# F50_cryocooler_controller.net
KiCad netlist of a schematic drawn in EAGLE
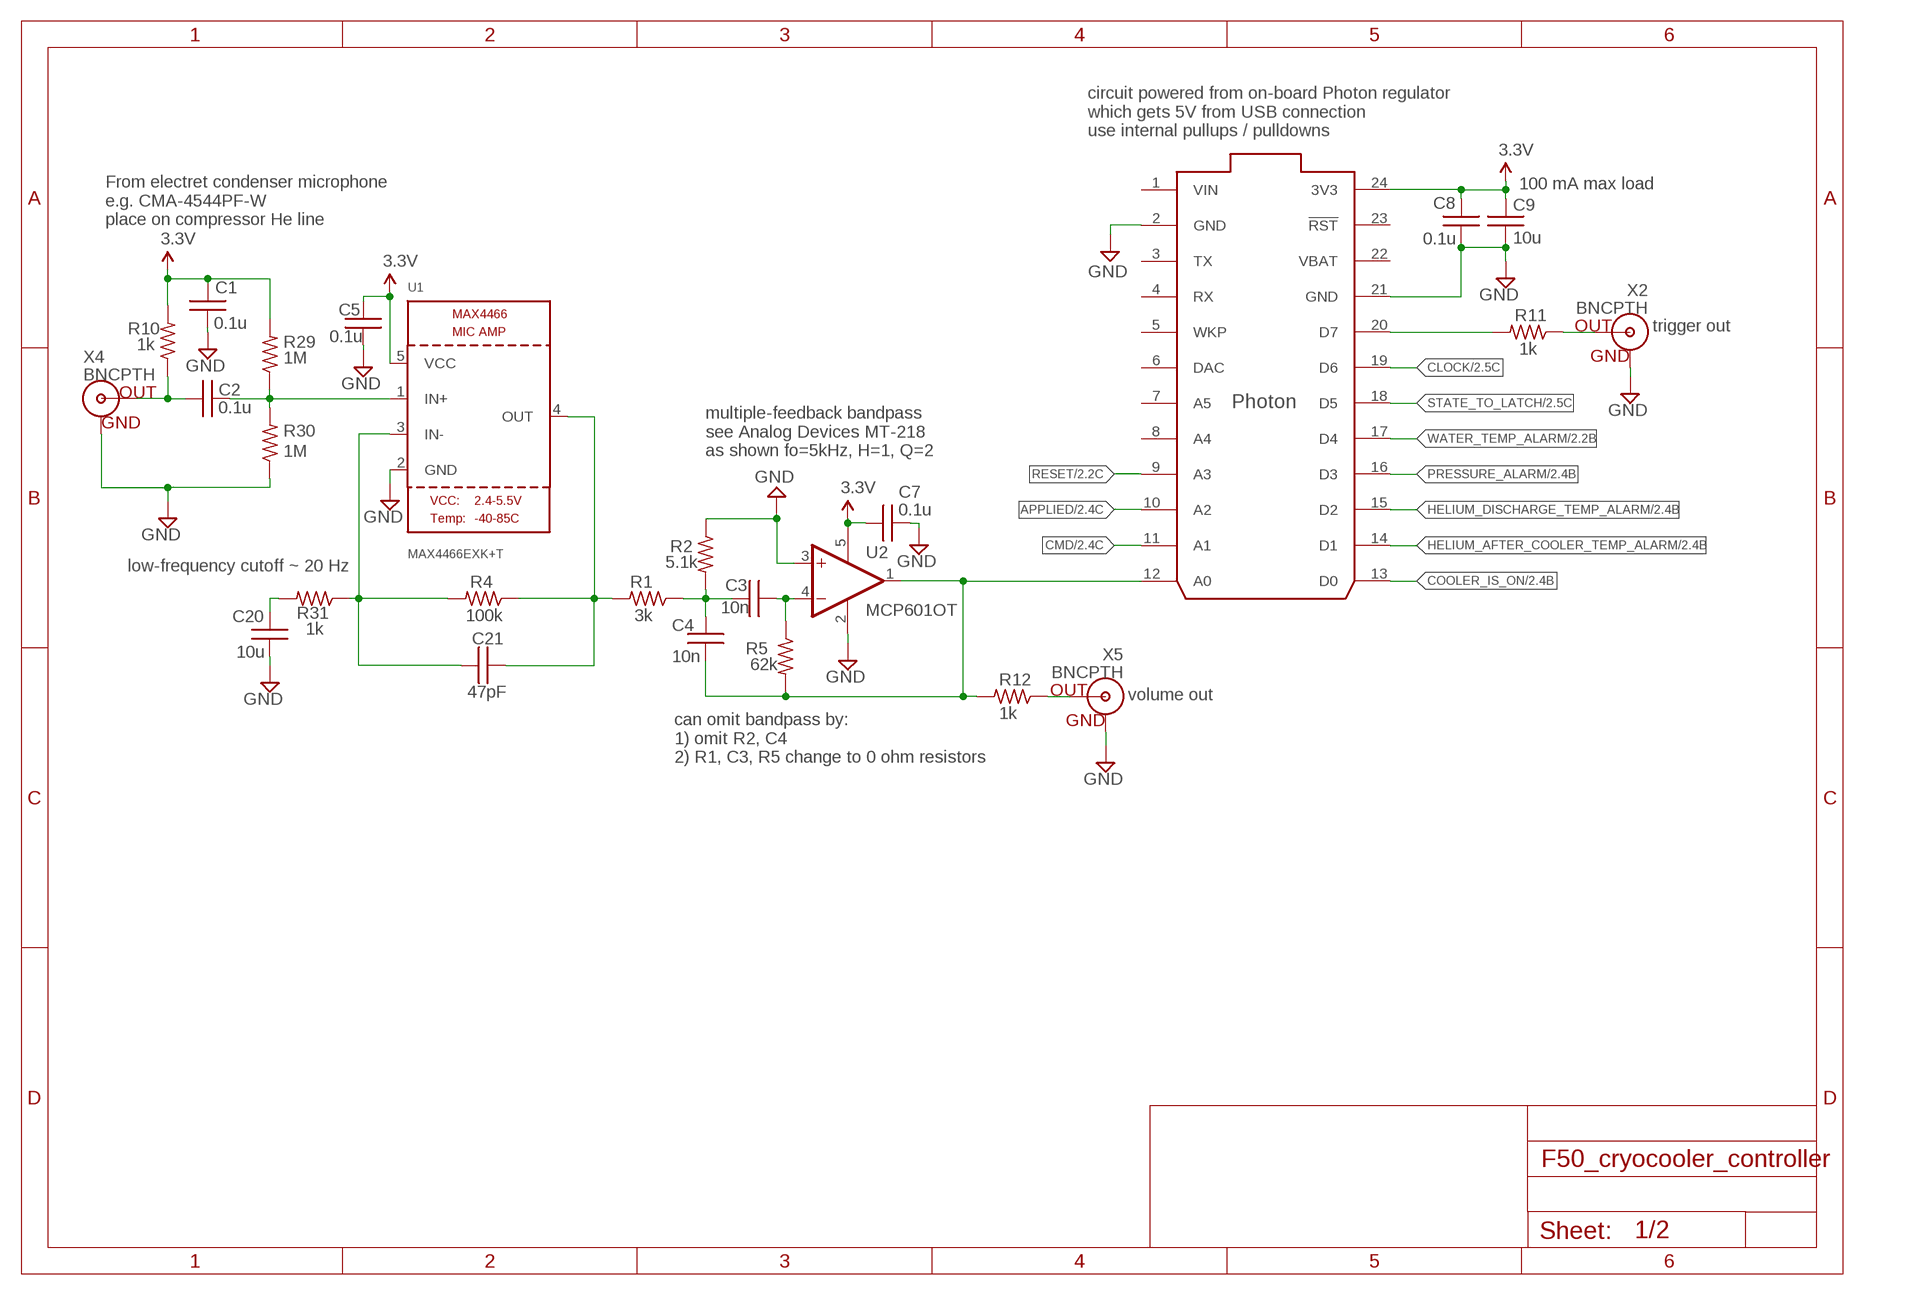
[diagram p0: schematic, sheet 1]
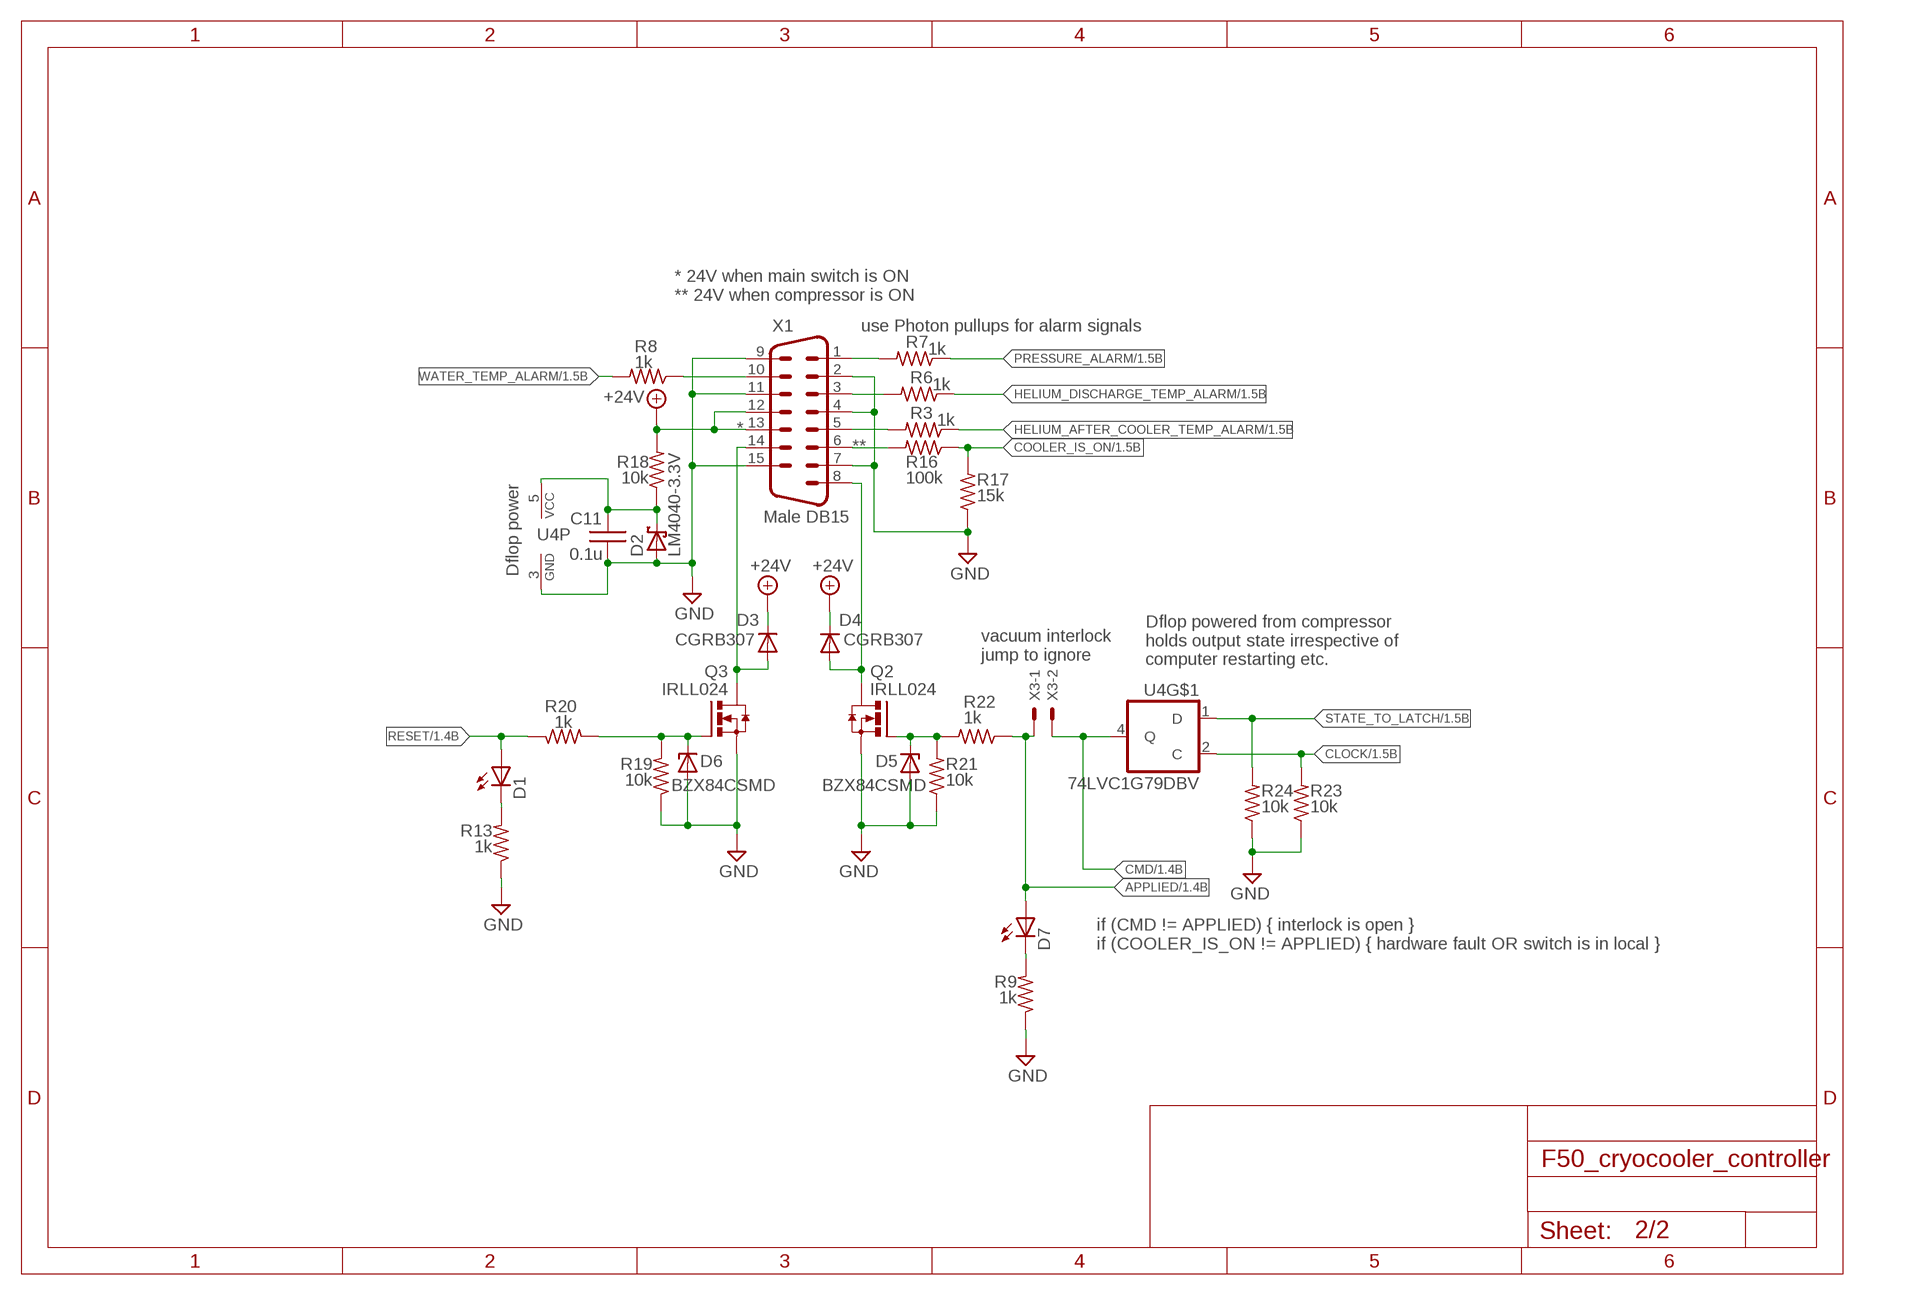
[diagram p1: schematic, sheet 2]

(export (version "E")
  (design (tool "Eeschema 10.0.6"))
  (components
    (comp (ref "C11")
      (value "0.1u")
      (footprint "eagle-import:0603")
      (libsource (lib "eagle-import") (part "C0603"))
    )
    (comp (ref "D1")
      (value "LED0603")
      (footprint "eagle-import:LED0603")
      (libsource (lib "eagle-import") (part "LED0603"))
    )
    (comp (ref "D2")
      (value "LM4040-3.3V")
      (footprint "eagle-import:SOT23")
      (libsource (lib "eagle-import") (part "LM4040"))
    )
    (comp (ref "D3")
      (value "CGRB307")
      (footprint "eagle-import:DO214AA")
      (libsource (lib "eagle-import") (part "DIODE-DO214AA"))
    )
    (comp (ref "D4")
      (value "CGRB307")
      (footprint "eagle-import:DO214AA")
      (libsource (lib "eagle-import") (part "DIODE-DO214AA"))
    )
    (comp (ref "D5")
      (value "BZX84CSMD")
      (footprint "eagle-import:TO236")
      (libsource (lib "eagle-import") (part "BZX84CSMD"))
    )
    (comp (ref "D6")
      (value "BZX84CSMD")
      (footprint "eagle-import:TO236")
      (libsource (lib "eagle-import") (part "BZX84CSMD"))
    )
    (comp (ref "D7")
      (value "LED0603")
      (footprint "eagle-import:LED0603")
      (libsource (lib "eagle-import") (part "LED0603"))
    )
    (comp (ref "Q2")
      (value "IRLL024")
      (footprint "eagle-import:SOT223")
      (libsource (lib "eagle-import") (part "N-HEXFET_?-SOT323IRLL014N"))
    )
    (comp (ref "Q3")
      (value "IRLL024")
      (footprint "eagle-import:SOT223")
      (libsource (lib "eagle-import") (part "N-HEXFET_?-SOT323IRLL014N"))
    )
    (comp (ref "R3")
      (value "1k")
      (footprint "eagle-import:0603")
      (libsource (lib "eagle-import") (part "R0603"))
    )
    (comp (ref "R6")
      (value "1k")
      (footprint "eagle-import:0603")
      (libsource (lib "eagle-import") (part "R0603"))
    )
    (comp (ref "R7")
      (value "1k")
      (footprint "eagle-import:0603")
      (libsource (lib "eagle-import") (part "R0603"))
    )
    (comp (ref "R8")
      (value "1k")
      (footprint "eagle-import:0603")
      (libsource (lib "eagle-import") (part "R0603"))
    )
    (comp (ref "R9")
      (value "1k")
      (footprint "eagle-import:0603")
      (libsource (lib "eagle-import") (part "R0603"))
    )
    (comp (ref "R13")
      (value "1k")
      (footprint "eagle-import:0603")
      (libsource (lib "eagle-import") (part "R0603"))
    )
    (comp (ref "R16")
      (value "100k")
      (footprint "eagle-import:0603")
      (libsource (lib "eagle-import") (part "R0603"))
    )
    (comp (ref "R17")
      (value "15k")
      (footprint "eagle-import:0603")
      (libsource (lib "eagle-import") (part "R0603"))
    )
    (comp (ref "R18")
      (value "10k")
      (footprint "eagle-import:0603")
      (libsource (lib "eagle-import") (part "R0603"))
    )
    (comp (ref "R19")
      (value "10k")
      (footprint "eagle-import:0603")
      (libsource (lib "eagle-import") (part "R0603"))
    )
    (comp (ref "R20")
      (value "1k")
      (footprint "eagle-import:0603")
      (libsource (lib "eagle-import") (part "R0603"))
    )
    (comp (ref "R21")
      (value "10k")
      (footprint "eagle-import:0603")
      (libsource (lib "eagle-import") (part "R0603"))
    )
    (comp (ref "R22")
      (value "1k")
      (footprint "eagle-import:0603")
      (libsource (lib "eagle-import") (part "R0603"))
    )
    (comp (ref "R23")
      (value "10k")
      (footprint "eagle-import:0603")
      (libsource (lib "eagle-import") (part "R0603"))
    )
    (comp (ref "R24")
      (value "10k")
      (footprint "eagle-import:0603")
      (libsource (lib "eagle-import") (part "R0603"))
    )
    (comp (ref "U4")
      (value "74LVC1G79DBV")
      (footprint "eagle-import:SOT23-5")
      (libsource (lib "eagle-import") (part "741G79DBVLVC"))
    )
    (comp (ref "X1")
      (value "Male DB15")
      (footprint "eagle-import:M15HP")
      (libsource (lib "eagle-import") (part "M15HP"))
    )
    (comp (ref "X3")
      (value "22-23-2021")
      (footprint "eagle-import:22-23-2021")
      (fields (field (name "MF") "MOLEX"))
      (libsource (lib "eagle-import") (part "22-23-2021"))
    )
    (comp (ref "C1")
      (value "0.1u")
      (footprint "eagle-import:0603")
      (libsource (lib "eagle-import") (part "C0603"))
    )
    (comp (ref "C2")
      (value "0.1u")
      (footprint "eagle-import:0603")
      (libsource (lib "eagle-import") (part "C0603"))
    )
    (comp (ref "C3")
      (value "10n")
      (footprint "eagle-import:0603")
      (libsource (lib "eagle-import") (part "C0603"))
    )
    (comp (ref "C4")
      (value "10n")
      (footprint "eagle-import:0603")
      (libsource (lib "eagle-import") (part "C0603"))
    )
    (comp (ref "C5")
      (value "0.1u")
      (footprint "eagle-import:0603")
      (libsource (lib "eagle-import") (part "C0603"))
    )
    (comp (ref "C7")
      (value "0.1u")
      (footprint "eagle-import:0603")
      (libsource (lib "eagle-import") (part "C0603"))
    )
    (comp (ref "C8")
      (value "0.1u")
      (footprint "eagle-import:0603")
      (libsource (lib "eagle-import") (part "C0603"))
    )
    (comp (ref "C9")
      (value "10u")
      (footprint "eagle-import:0805")
      (libsource (lib "eagle-import") (part "C0805"))
    )
    (comp (ref "C20")
      (value "10u")
      (footprint "eagle-import:0603")
      (libsource (lib "eagle-import") (part "C0603"))
    )
    (comp (ref "C21")
      (value "47pF")
      (footprint "eagle-import:0603")
      (libsource (lib "eagle-import") (part "C0603"))
    )
    (comp (ref "R1")
      (value "3k")
      (footprint "eagle-import:0603")
      (libsource (lib "eagle-import") (part "R0603"))
    )
    (comp (ref "R2")
      (value "5.1k")
      (footprint "eagle-import:0603")
      (libsource (lib "eagle-import") (part "R0603"))
    )
    (comp (ref "R4")
      (value "100k")
      (footprint "eagle-import:0603")
      (libsource (lib "eagle-import") (part "R0603"))
    )
    (comp (ref "R5")
      (value "62k")
      (footprint "eagle-import:0603")
      (libsource (lib "eagle-import") (part "R0603"))
    )
    (comp (ref "R10")
      (value "1k")
      (footprint "eagle-import:0603")
      (libsource (lib "eagle-import") (part "R0603"))
    )
    (comp (ref "R11")
      (value "1k")
      (footprint "eagle-import:0603")
      (libsource (lib "eagle-import") (part "R0603"))
    )
    (comp (ref "R12")
      (value "1k")
      (footprint "eagle-import:0603")
      (libsource (lib "eagle-import") (part "R0603"))
    )
    (comp (ref "R29")
      (value "1M")
      (footprint "eagle-import:0603")
      (libsource (lib "eagle-import") (part "R0603"))
    )
    (comp (ref "R30")
      (value "1M")
      (footprint "eagle-import:0603")
      (libsource (lib "eagle-import") (part "R0603"))
    )
    (comp (ref "R31")
      (value "1k")
      (footprint "eagle-import:0603")
      (libsource (lib "eagle-import") (part "R0603"))
    )
    (comp (ref "U1")
      (value "MAX4466EXK+T")
      (footprint "eagle-import:SC70-5")
      (libsource (lib "eagle-import") (part "MAX4466{dblquote}{dblquote}"))
    )
    (comp (ref "U2")
      (value "MCP601OT")
      (footprint "eagle-import:SOT23-5")
      (libsource (lib "eagle-import") (part "MCP601OT"))
    )
    (comp (ref "U3")
      (value "PHOTON_WITH_HEADERS")
      (footprint "eagle-import:PHOTON")
      (libsource (lib "eagle-import") (part "PHOTON_WITH_HEADERS"))
    )
    (comp (ref "X2")
      (value "BNCPTH")
      (footprint "eagle-import:BNC")
      (libsource (lib "eagle-import") (part "BNCPTH"))
    )
    (comp (ref "X4")
      (value "BNCPTH")
      (footprint "eagle-import:BNC")
      (libsource (lib "eagle-import") (part "BNCPTH"))
    )
    (comp (ref "X5")
      (value "BNCPTH")
      (footprint "eagle-import:BNC")
      (libsource (lib "eagle-import") (part "BNCPTH"))
    )
  )
  (nets
    (net (code "1") (name "+24V") (class "Default")
      (node (ref "D3") (pin "C") (pinfunction "C_C") (pintype "passive"))
      (node (ref "D4") (pin "C") (pinfunction "C_C") (pintype "passive"))
      (node (ref "R18") (pin "2") (pinfunction "2_2") (pintype "passive"))
      (node (ref "X1") (pin "12") (pinfunction "12_12") (pintype "passive"))
      (node (ref "X1") (pin "13") (pinfunction "13_13") (pintype "passive"))
    )
    (net (code "2") (name "3.3V") (class "Default")
      (node (ref "C1") (pin "1") (pinfunction "1_1") (pintype "passive"))
      (node (ref "C5") (pin "1") (pinfunction "1_1") (pintype "passive"))
      (node (ref "C7") (pin "1") (pinfunction "1_1") (pintype "passive"))
      (node (ref "C8") (pin "1") (pinfunction "1_1") (pintype "passive"))
      (node (ref "C9") (pin "2") (pinfunction "2_2") (pintype "passive"))
      (node (ref "R10") (pin "2") (pinfunction "2_2") (pintype "passive"))
      (node (ref "R29") (pin "2") (pinfunction "2_2") (pintype "passive"))
      (node (ref "U1") (pin "5") (pinfunction "VCC_5") (pintype "bidirectional"))
      (node (ref "U2") (pin "5") (pinfunction "V+_5") (pintype "power_in"))
      (node (ref "U3") (pin "24") (pinfunction "3V3_24") (pintype "power_in"))
    )
    (net (code "3") (name "APPLIED") (class "Default")
      (node (ref "D7") (pin "A") (pinfunction "A_A") (pintype "passive"))
      (node (ref "R22") (pin "1") (pinfunction "1_1") (pintype "passive"))
      (node (ref "U3") (pin "10") (pinfunction "A2_10") (pintype "bidirectional"))
      (node (ref "X3") (pin "1") (pinfunction "S_1") (pintype "passive"))
    )
    (net (code "4") (name "CLOCK") (class "Default")
      (node (ref "R23") (pin "2") (pinfunction "2_2") (pintype "passive"))
      (node (ref "U3") (pin "19") (pinfunction "D6_19") (pintype "bidirectional"))
      (node (ref "U4") (pin "2") (pinfunction "C_2") (pintype "input"))
    )
    (net (code "5") (name "CMD") (class "Default")
      (node (ref "U3") (pin "11") (pinfunction "A1_11") (pintype "bidirectional"))
      (node (ref "U4") (pin "4") (pinfunction "Q_4") (pintype "output"))
      (node (ref "X3") (pin "2") (pinfunction "S_2") (pintype "passive"))
    )
    (net (code "6") (name "COOLER_IS_ON") (class "Default")
      (node (ref "R16") (pin "1") (pinfunction "1_1") (pintype "passive"))
      (node (ref "R17") (pin "2") (pinfunction "2_2") (pintype "passive"))
      (node (ref "U3") (pin "13") (pinfunction "D0_13") (pintype "bidirectional"))
    )
    (net (code "7") (name "GND") (class "Default")
      (node (ref "C1") (pin "2") (pinfunction "2_2") (pintype "passive"))
      (node (ref "C11") (pin "2") (pinfunction "2_2") (pintype "passive"))
      (node (ref "C20") (pin "2") (pinfunction "2_2") (pintype "passive"))
      (node (ref "C5") (pin "2") (pinfunction "2_2") (pintype "passive"))
      (node (ref "C7") (pin "2") (pinfunction "2_2") (pintype "passive"))
      (node (ref "C8") (pin "2") (pinfunction "2_2") (pintype "passive"))
      (node (ref "C9") (pin "1") (pinfunction "1_1") (pintype "passive"))
      (node (ref "D2") (pin "2") (pinfunction "A_2") (pintype "passive"))
      (node (ref "D5") (pin "A") (pinfunction "A_A") (pintype "passive"))
      (node (ref "D6") (pin "A") (pinfunction "A_A") (pintype "passive"))
      (node (ref "Q2") (pin "3") (pinfunction "S_3") (pintype "passive"))
      (node (ref "Q3") (pin "3") (pinfunction "S_3") (pintype "passive"))
      (node (ref "R13") (pin "1") (pinfunction "1_1") (pintype "passive"))
      (node (ref "R17") (pin "1") (pinfunction "1_1") (pintype "passive"))
      (node (ref "R19") (pin "1") (pinfunction "1_1") (pintype "passive"))
      (node (ref "R2") (pin "1") (pinfunction "1_1") (pintype "passive"))
      (node (ref "R21") (pin "1") (pinfunction "1_1") (pintype "passive"))
      (node (ref "R23") (pin "1") (pinfunction "1_1") (pintype "passive"))
      (node (ref "R24") (pin "1") (pinfunction "1_1") (pintype "passive"))
      (node (ref "R30") (pin "1") (pinfunction "1_1") (pintype "passive"))
      (node (ref "R9") (pin "1") (pinfunction "1_1") (pintype "passive"))
      (node (ref "U1") (pin "2") (pinfunction "GND_2") (pintype "bidirectional"))
      (node (ref "U2") (pin "2") (pinfunction "V-_2") (pintype "power_in"))
      (node (ref "U2") (pin "3") (pinfunction "+IN_3") (pintype "input"))
      (node (ref "U3") (pin "2") (pinfunction "GND_2") (pintype "power_in"))
      (node (ref "U3") (pin "21") (pinfunction "GND_21") (pintype "power_in"))
      (node (ref "U4") (pin "3") (pinfunction "GND_3") (pintype "power_in"))
      (node (ref "X1") (pin "11") (pinfunction "11_11") (pintype "passive"))
      (node (ref "X1") (pin "15") (pinfunction "15_15") (pintype "passive"))
      (node (ref "X1") (pin "2") (pinfunction "2_2") (pintype "passive"))
      (node (ref "X1") (pin "4") (pinfunction "4_4") (pintype "passive"))
      (node (ref "X1") (pin "7") (pinfunction "7_7") (pintype "passive"))
      (node (ref "X1") (pin "9") (pinfunction "9_9") (pintype "passive"))
      (node (ref "X2") (pin "GND") (pinfunction "GND_GND") (pintype "bidirectional"))
      (node (ref "X4") (pin "GND") (pinfunction "GND_GND") (pintype "bidirectional"))
      (node (ref "X5") (pin "GND") (pinfunction "GND_GND") (pintype "bidirectional"))
    )
    (net (code "8") (name "HELIUM_AFTER_COOLER_TEMP_ALARM") (class "Default")
      (node (ref "R3") (pin "1") (pinfunction "1_1") (pintype "passive"))
      (node (ref "U3") (pin "14") (pinfunction "D1_14") (pintype "bidirectional"))
    )
    (net (code "9") (name "HELIUM_DISCHARGE_TEMP_ALARM") (class "Default")
      (node (ref "R6") (pin "1") (pinfunction "1_1") (pintype "passive"))
      (node (ref "U3") (pin "15") (pinfunction "D2_15") (pintype "bidirectional"))
    )
    (net (code "10") (name "Net-(C3-Pad1)") (class "Default")
      (node (ref "C3") (pin "1") (pinfunction "1_1") (pintype "passive"))
      (node (ref "C4") (pin "2") (pinfunction "2_2") (pintype "passive"))
      (node (ref "R1") (pin "1") (pinfunction "1_1") (pintype "passive"))
      (node (ref "R2") (pin "2") (pinfunction "2_2") (pintype "passive"))
    )
    (net (code "11") (name "Net-(C20-Pad1)") (class "Default")
      (node (ref "C20") (pin "1") (pinfunction "1_1") (pintype "passive"))
      (node (ref "R31") (pin "2") (pinfunction "2_2") (pintype "passive"))
    )
    (net (code "12") (name "Net-(D1-PadC)") (class "Default")
      (node (ref "D1") (pin "C") (pinfunction "C_C") (pintype "passive"))
      (node (ref "R13") (pin "2") (pinfunction "2_2") (pintype "passive"))
    )
    (net (code "13") (name "Net-(D2-C)") (class "Default")
      (node (ref "C11") (pin "1") (pinfunction "1_1") (pintype "passive"))
      (node (ref "D2") (pin "1") (pinfunction "C_1") (pintype "passive"))
      (node (ref "R18") (pin "1") (pinfunction "1_1") (pintype "passive"))
      (node (ref "U4") (pin "5") (pinfunction "VCC_5") (pintype "power_in"))
    )
    (net (code "14") (name "Net-(D7-PadC)") (class "Default")
      (node (ref "D7") (pin "C") (pinfunction "C_C") (pintype "passive"))
      (node (ref "R9") (pin "2") (pinfunction "2_2") (pintype "passive"))
    )
    (net (code "15") (name "Net-(Q2-D)") (class "Default")
      (node (ref "D4") (pin "A") (pinfunction "A_A") (pintype "passive"))
      (node (ref "Q2") (pin "4") (pinfunction "D_4") (pintype "passive"))
      (node (ref "X1") (pin "8") (pinfunction "8_8") (pintype "passive"))
    )
    (net (code "16") (name "Net-(Q2-G)") (class "Default")
      (node (ref "D5") (pin "C") (pinfunction "C_C") (pintype "passive"))
      (node (ref "Q2") (pin "1") (pinfunction "G_1") (pintype "passive"))
      (node (ref "R21") (pin "2") (pinfunction "2_2") (pintype "passive"))
      (node (ref "R22") (pin "2") (pinfunction "2_2") (pintype "passive"))
    )
    (net (code "17") (name "Net-(Q3-D)") (class "Default")
      (node (ref "D3") (pin "A") (pinfunction "A_A") (pintype "passive"))
      (node (ref "Q3") (pin "4") (pinfunction "D_4") (pintype "passive"))
      (node (ref "X1") (pin "14") (pinfunction "14_14") (pintype "passive"))
    )
    (net (code "18") (name "Net-(Q3-G)") (class "Default")
      (node (ref "D6") (pin "C") (pinfunction "C_C") (pintype "passive"))
      (node (ref "Q3") (pin "1") (pinfunction "G_1") (pintype "passive"))
      (node (ref "R19") (pin "2") (pinfunction "2_2") (pintype "passive"))
      (node (ref "R20") (pin "2") (pinfunction "2_2") (pintype "passive"))
    )
    (net (code "19") (name "Net-(R3-Pad2)") (class "Default")
      (node (ref "R3") (pin "2") (pinfunction "2_2") (pintype "passive"))
      (node (ref "X1") (pin "5") (pinfunction "5_5") (pintype "passive"))
    )
    (net (code "20") (name "Net-(R6-Pad2)") (class "Default")
      (node (ref "R6") (pin "2") (pinfunction "2_2") (pintype "passive"))
      (node (ref "X1") (pin "3") (pinfunction "3_3") (pintype "passive"))
    )
    (net (code "21") (name "Net-(R7-Pad2)") (class "Default")
      (node (ref "R7") (pin "2") (pinfunction "2_2") (pintype "passive"))
      (node (ref "X1") (pin "1") (pinfunction "1_1") (pintype "passive"))
    )
    (net (code "22") (name "Net-(R8-Pad1)") (class "Default")
      (node (ref "R8") (pin "1") (pinfunction "1_1") (pintype "passive"))
      (node (ref "X1") (pin "10") (pinfunction "10_10") (pintype "passive"))
    )
    (net (code "23") (name "Net-(R16-Pad2)") (class "Default")
      (node (ref "R16") (pin "2") (pinfunction "2_2") (pintype "passive"))
      (node (ref "X1") (pin "6") (pinfunction "6_6") (pintype "passive"))
    )
    (net (code "24") (name "Net-(U1-IN+)") (class "Default")
      (node (ref "C2") (pin "2") (pinfunction "2_2") (pintype "passive"))
      (node (ref "R29") (pin "1") (pinfunction "1_1") (pintype "passive"))
      (node (ref "R30") (pin "2") (pinfunction "2_2") (pintype "passive"))
      (node (ref "U1") (pin "1") (pinfunction "IN+_1") (pintype "bidirectional"))
    )
    (net (code "25") (name "Net-(U1-IN-)") (class "Default")
      (node (ref "C21") (pin "1") (pinfunction "1_1") (pintype "passive"))
      (node (ref "R31") (pin "1") (pinfunction "1_1") (pintype "passive"))
      (node (ref "R4") (pin "2") (pinfunction "2_2") (pintype "passive"))
      (node (ref "U1") (pin "3") (pinfunction "IN-_3") (pintype "bidirectional"))
    )
    (net (code "26") (name "Net-(U1-OUT)") (class "Default")
      (node (ref "C21") (pin "2") (pinfunction "2_2") (pintype "passive"))
      (node (ref "R1") (pin "2") (pinfunction "2_2") (pintype "passive"))
      (node (ref "R4") (pin "1") (pinfunction "1_1") (pintype "passive"))
      (node (ref "U1") (pin "4") (pinfunction "OUT_4") (pintype "bidirectional"))
    )
    (net (code "27") (name "Net-(U2--IN)") (class "Default")
      (node (ref "C3") (pin "2") (pinfunction "2_2") (pintype "passive"))
      (node (ref "R5") (pin "1") (pinfunction "1_1") (pintype "passive"))
      (node (ref "U2") (pin "4") (pinfunction "-IN_4") (pintype "input"))
    )
    (net (code "28") (name "Net-(U2-OUT)") (class "Default")
      (node (ref "C4") (pin "1") (pinfunction "1_1") (pintype "passive"))
      (node (ref "R12") (pin "2") (pinfunction "2_2") (pintype "passive"))
      (node (ref "R5") (pin "2") (pinfunction "2_2") (pintype "passive"))
      (node (ref "U2") (pin "1") (pinfunction "OUT_1") (pintype "output"))
      (node (ref "U3") (pin "12") (pinfunction "A0_12") (pintype "bidirectional"))
    )
    (net (code "29") (name "Net-(U3-D7)") (class "Default")
      (node (ref "R11") (pin "2") (pinfunction "2_2") (pintype "passive"))
      (node (ref "U3") (pin "20") (pinfunction "D7_20") (pintype "bidirectional"))
    )
    (net (code "30") (name "Net-(X2-OUT)") (class "Default")
      (node (ref "R11") (pin "1") (pinfunction "1_1") (pintype "passive"))
      (node (ref "X2") (pin "S") (pinfunction "OUT_S") (pintype "bidirectional"))
    )
    (net (code "31") (name "Net-(X4-OUT)") (class "Default")
      (node (ref "C2") (pin "1") (pinfunction "1_1") (pintype "passive"))
      (node (ref "R10") (pin "1") (pinfunction "1_1") (pintype "passive"))
      (node (ref "X4") (pin "S") (pinfunction "OUT_S") (pintype "bidirectional"))
    )
    (net (code "32") (name "Net-(X5-OUT)") (class "Default")
      (node (ref "R12") (pin "1") (pinfunction "1_1") (pintype "passive"))
      (node (ref "X5") (pin "S") (pinfunction "OUT_S") (pintype "bidirectional"))
    )
    (net (code "33") (name "PRESSURE_ALARM") (class "Default")
      (node (ref "R7") (pin "1") (pinfunction "1_1") (pintype "passive"))
      (node (ref "U3") (pin "16") (pinfunction "D3_16") (pintype "bidirectional"))
    )
    (net (code "34") (name "RESET") (class "Default")
      (node (ref "D1") (pin "A") (pinfunction "A_A") (pintype "passive"))
      (node (ref "R20") (pin "1") (pinfunction "1_1") (pintype "passive"))
      (node (ref "U3") (pin "9") (pinfunction "A3_9") (pintype "bidirectional"))
    )
    (net (code "35") (name "STATE_TO_LATCH") (class "Default")
      (node (ref "R24") (pin "2") (pinfunction "2_2") (pintype "passive"))
      (node (ref "U3") (pin "18") (pinfunction "D5_18") (pintype "bidirectional"))
      (node (ref "U4") (pin "1") (pinfunction "D_1") (pintype "input"))
    )
    (net (code "36") (name "VBAT") (class "Default")
      (node (ref "U3") (pin "22") (pinfunction "VBAT_22") (pintype "power_in"))
    )
    (net (code "37") (name "VIN") (class "Default")
      (node (ref "U3") (pin "1") (pinfunction "VIN_1") (pintype "power_in"))
    )
    (net (code "38") (name "WATER_TEMP_ALARM") (class "Default")
      (node (ref "R8") (pin "2") (pinfunction "2_2") (pintype "passive"))
      (node (ref "U3") (pin "17") (pinfunction "D4_17") (pintype "bidirectional"))
    )
    (net (code "39") (name "unconnected-(U3-A4-Pad8)") (class "Default")
      (node (ref "U3") (pin "8") (pinfunction "A4_8") (pintype "bidirectional"))
    )
    (net (code "40") (name "unconnected-(U3-A5-Pad7)") (class "Default")
      (node (ref "U3") (pin "7") (pinfunction "A5_7") (pintype "bidirectional"))
    )
    (net (code "41") (name "unconnected-(U3-DAC-Pad6)") (class "Default")
      (node (ref "U3") (pin "6") (pinfunction "DAC_6") (pintype "bidirectional"))
    )
    (net (code "42") (name "unconnected-(U3-RX-Pad4)") (class "Default")
      (node (ref "U3") (pin "4") (pinfunction "RX_4") (pintype "bidirectional"))
    )
    (net (code "43") (name "unconnected-(U3-TX-Pad3)") (class "Default")
      (node (ref "U3") (pin "3") (pinfunction "TX_3") (pintype "bidirectional"))
    )
    (net (code "44") (name "unconnected-(U3-WKP-Pad5)") (class "Default")
      (node (ref "U3") (pin "5") (pinfunction "WKP_5") (pintype "bidirectional"))
    )
    (net (code "45") (name "unconnected-(U3-~{RST}-Pad23)") (class "Default")
      (node (ref "U3") (pin "23") (pinfunction "~{RST}_23") (pintype "bidirectional"))
    )
  )
)
